# daisy_chain_connectors.net
KiCad netlist of a schematic drawn in Altium Designer
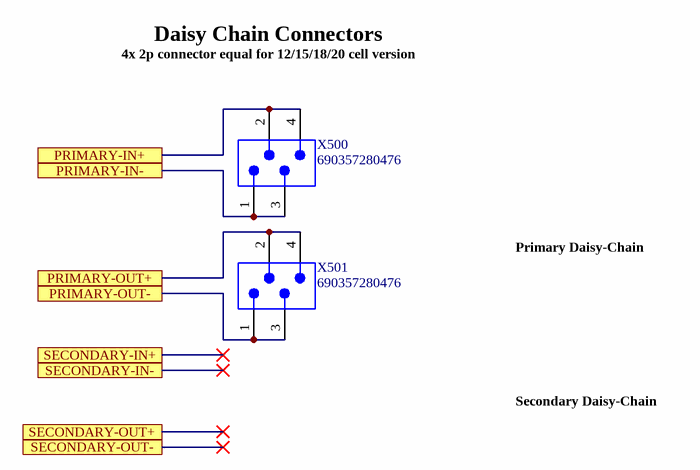
[diagram p0: daisy_chain_connectors.SchDoc]

(export (version "E")
  (design (tool "Eeschema 10.0.6"))
  (components
    (comp (ref "X500")
      (value "690357280476")
      (footprint "690357280476")
      (libsource (lib "Altium Content Vault") (part "MM_Male_04P"))
    )
    (comp (ref "X501")
      (value "690357280476")
      (footprint "690357280476")
      (libsource (lib "Altium Content Vault") (part "MM_Male_04P"))
    )
  )
  (nets
    (net (code "1") (name "/PRIMARY-IN+") (class "Default")
      (node (ref "X500") (pin "2") (pinfunction "2_2") (pintype "passive"))
      (node (ref "X500") (pin "4") (pinfunction "4_4") (pintype "passive"))
    )
    (net (code "2") (name "/PRIMARY-IN-") (class "Default")
      (node (ref "X500") (pin "1") (pinfunction "1_1") (pintype "passive"))
      (node (ref "X500") (pin "3") (pinfunction "3_3") (pintype "passive"))
    )
    (net (code "3") (name "/PRIMARY-OUT+") (class "Default")
      (node (ref "X501") (pin "2") (pinfunction "2_2") (pintype "passive"))
      (node (ref "X501") (pin "4") (pinfunction "4_4") (pintype "passive"))
    )
    (net (code "4") (name "/PRIMARY-OUT-") (class "Default")
      (node (ref "X501") (pin "1") (pinfunction "1_1") (pintype "passive"))
      (node (ref "X501") (pin "3") (pinfunction "3_3") (pintype "passive"))
    )
  )
)
